# SCH_PCB-Hacker-Jam_2024-06-07.net
KiCad netlist of a schematic drawn in EasyEDA
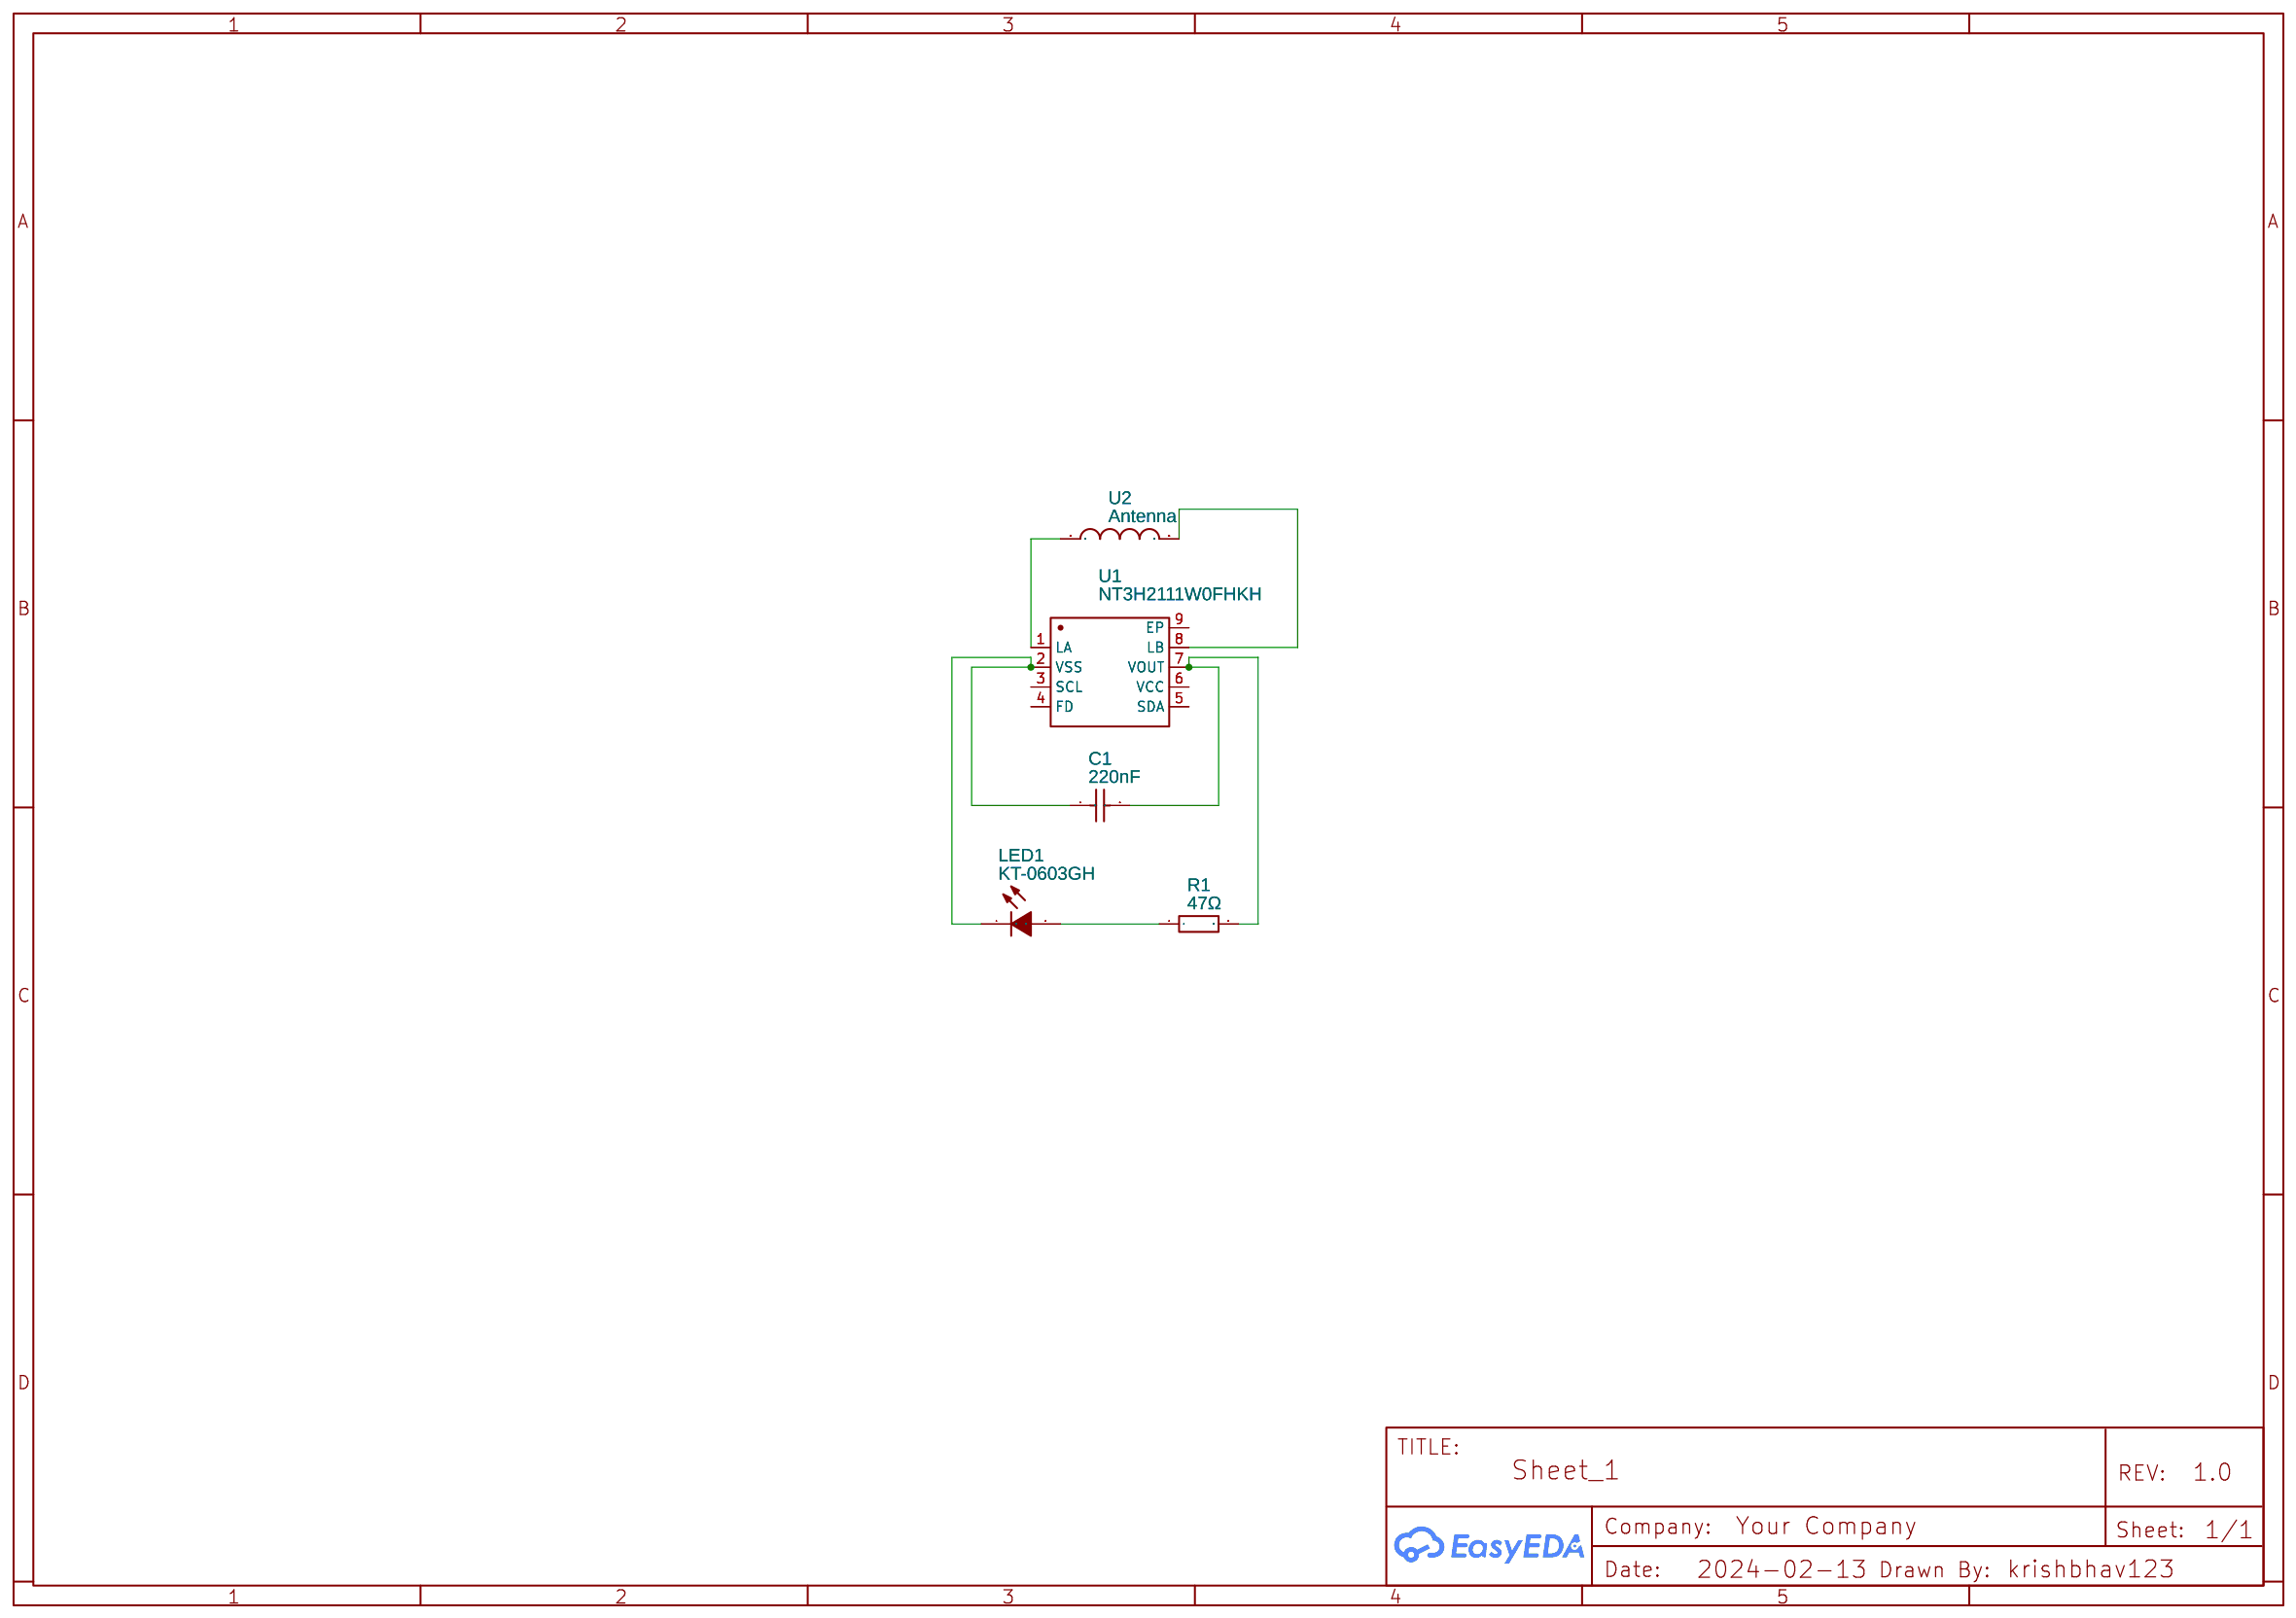
[diagram p0: schematic sheet]

(export (version "E")
  (design (tool "Eeschema 10.0.6"))
  (components
    (comp (ref "C1")
      (value "220nF")
      (fields
        (field (name "Manufacturer Part") "CL10B224KA8NNNC")
        (field (name "Manufacturer") "SAMSUNG(三星)")
      )
      (libsource (lib "") (part "CL10B224KA8NNNC"))
    )
    (comp (ref "LED1")
      (value "KT-0603GH")
      (fields (field (name "Manufacturer") "匡通"))
      (libsource (lib "") (part "KT-0603GH"))
    )
    (comp (ref "R1")
      (value "47Ω")
      (fields
        (field (name "Manufacturer Part") "0603WAF470JT5E")
        (field (name "Manufacturer") "UNI-ROYAL(厚声)")
      )
      (libsource (lib "") (part "0603WAF470JT5E"))
    )
    (comp (ref "U1")
      (value "NT3H2111W0FHKH")
      (fields (field (name "Manufacturer") "NXP(恩智浦)"))
      (libsource (lib "") (part "NT3H2111W0FHKH"))
    )
    (comp (ref "U2") (value "Antenna") (libsource (lib "") (part "Antenna")))
  )
  (nets
    (net (code "1") (name "Net-(LED1-A)") (class "Default")
      (node (ref "LED1") (pin "2") (pinfunction "A_2") (pintype "input"))
      (node (ref "R1") (pin "1") (pinfunction "1_1") (pintype "input"))
    )
    (net (code "2") (name "Net-(LED1-C)") (class "Default")
      (node (ref "C1") (pin "1") (pinfunction "1_1") (pintype "input"))
      (node (ref "LED1") (pin "1") (pinfunction "C_1") (pintype "input"))
      (node (ref "U1") (pin "2") (pinfunction "VSS_2") (pintype "unspecified"))
    )
    (net (code "3") (name "Net-(U1-LA)") (class "Default")
      (node (ref "U1") (pin "1") (pinfunction "LA_1") (pintype "unspecified"))
      (node (ref "U2") (pin "P$2") (pinfunction "P$2_P$2") (pintype "unspecified"))
    )
    (net (code "4") (name "Net-(U1-LB)") (class "Default")
      (node (ref "U1") (pin "8") (pinfunction "LB_8") (pintype "unspecified"))
      (node (ref "U2") (pin "P$1") (pinfunction "P$1_P$1") (pintype "unspecified"))
    )
    (net (code "5") (name "Net-(U1-VOUT)") (class "Default")
      (node (ref "C1") (pin "2") (pinfunction "2_2") (pintype "input"))
      (node (ref "R1") (pin "2") (pinfunction "2_2") (pintype "input"))
      (node (ref "U1") (pin "7") (pinfunction "VOUT_7") (pintype "unspecified"))
    )
    (net (code "6") (name "unconnected-(U1-EP-Pad9)") (class "Default")
      (node (ref "U1") (pin "9") (pinfunction "EP_9") (pintype "unspecified"))
    )
    (net (code "7") (name "unconnected-(U1-FD-Pad4)") (class "Default")
      (node (ref "U1") (pin "4") (pinfunction "FD_4") (pintype "unspecified"))
    )
    (net (code "8") (name "unconnected-(U1-SCL-Pad3)") (class "Default")
      (node (ref "U1") (pin "3") (pinfunction "SCL_3") (pintype "unspecified"))
    )
    (net (code "9") (name "unconnected-(U1-SDA-Pad5)") (class "Default")
      (node (ref "U1") (pin "5") (pinfunction "SDA_5") (pintype "unspecified"))
    )
    (net (code "10") (name "unconnected-(U1-VCC-Pad6)") (class "Default")
      (node (ref "U1") (pin "6") (pinfunction "VCC_6") (pintype "unspecified"))
    )
  )
)
